# PROC091F_AOP_IO.net
KiCad netlist of a schematic drawn in Altium Designer
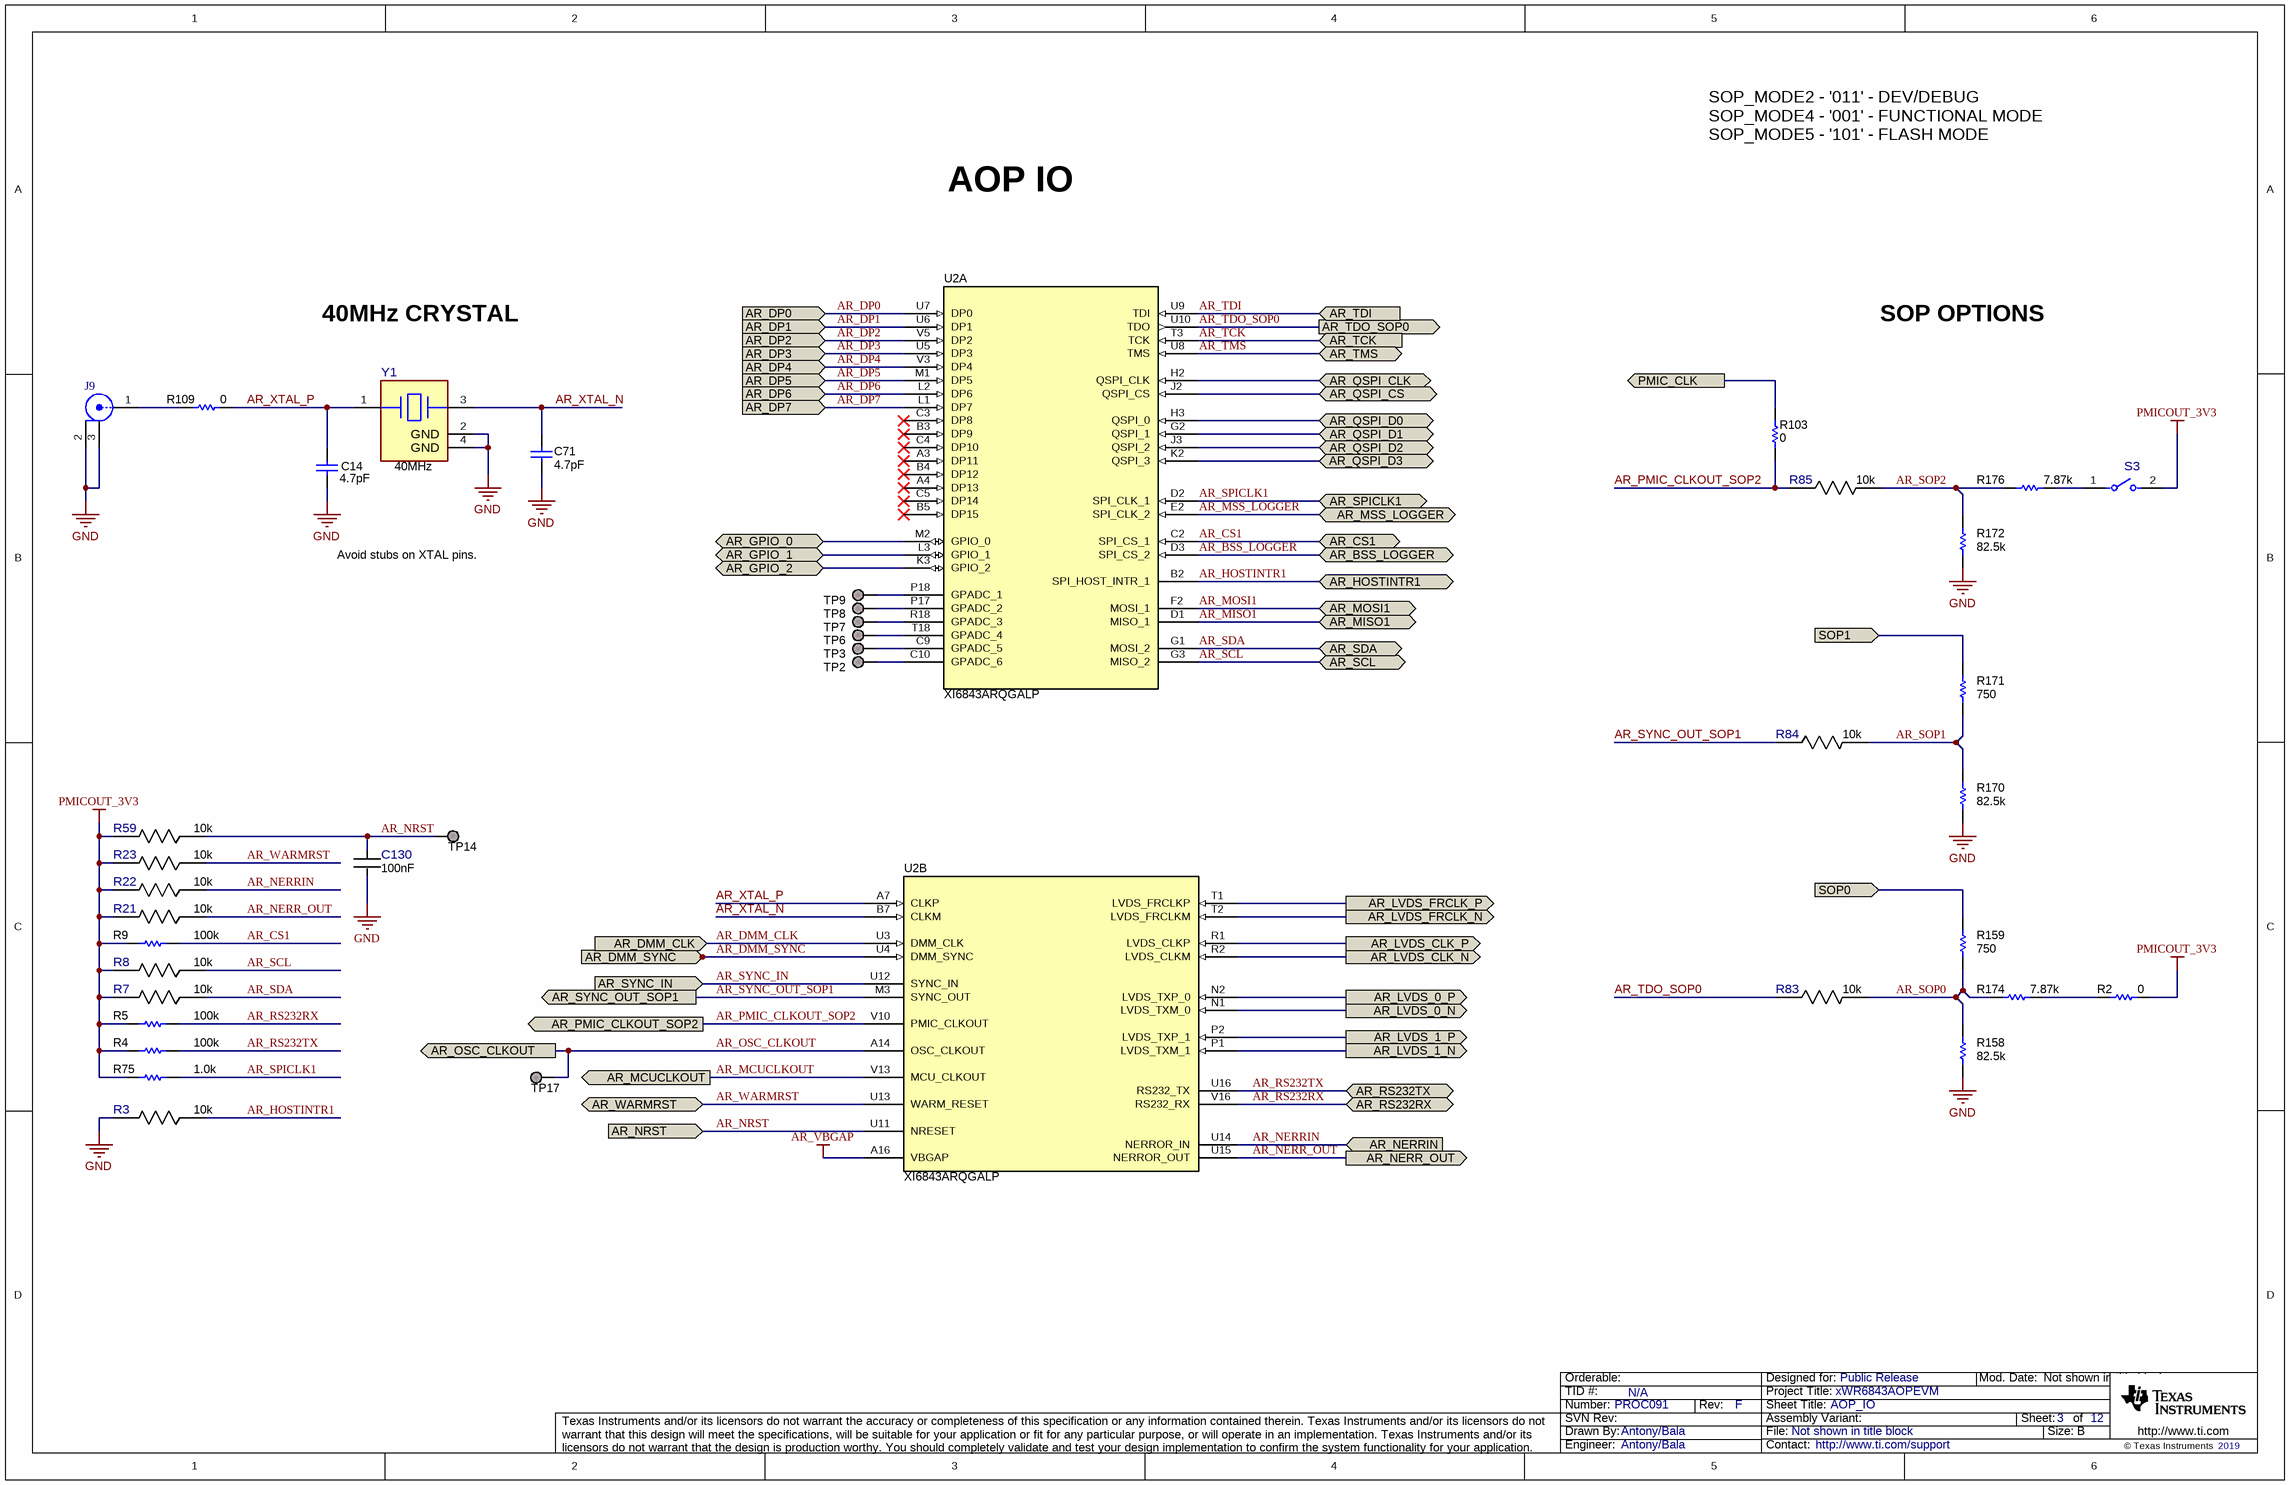
[diagram p0: PROC091F_AOP_IO.SchDoc]

(export (version "E")
  (design (tool "Eeschema 10.0.6"))
  (components
    (comp (ref "C14")
      (value "4.7pF")
      (footprint "0201_033L")
      (description "CAP, CERM, 4.7 pF, 50 V,+/- 3%, C0G/NP0, 0201")
      (fields (field (name "MANUFACTURER") "MuRata") (field (name "PARTNUMBER") "GRM0335C1H4R7BA01D"))
      (libsource (lib "Altium Vault - TI") (part "Capacitor"))
    )
    (comp (ref "C71")
      (value "4.7pF")
      (footprint "0201_033L")
      (description "CAP, CERM, 4.7 pF, 50 V,+/- 3%, C0G/NP0, 0201")
      (fields (field (name "MANUFACTURER") "MuRata") (field (name "PARTNUMBER") "GRM0335C1H4R7BA01D"))
      (libsource (lib "Altium Vault - TI") (part "Capacitor"))
    )
    (comp (ref "C130")
      (value "GRM033R6YA104KE14D")
      (footprint "FP-GRM033R6YA104KE14D_0201 (0603 Metric)-IPC_C")
      (description "Cap Ceramic 0.1uF 35V X5R 10% Pad SMD 0201 85C T/R")
      (fields (field (name "CAP_F") "100nF") (field (name "MANUFACTURER") "Murata Electronics North America"))
      (libsource (lib "Altium Vault - TI") (part "SYM-B32642B0223J"))
    )
    (comp (ref "J9")
      (value "U.FL-R-SMT-1(01)")
      (footprint "CONN_UFL-R-SMT-1")
      (description "Receptacle, Ultra Miniature Coaxial, Male Pin, 50 ohm, SMT")
      (fields
        (field (name "MANUFACTURER") "Hirose Electric Co. Ltd.")
        (field (name "PUBLISHER") "Texas Instruments")
      )
      (libsource (lib "Altium Vault - TI") (part "SMA_Contact1_GND23"))
    )
    (comp (ref "R2")
      (value "RC0201JR-070RL")
      (footprint "FP-RC0201JR-070RL_0201 (0603 Metric)-MFG")
      (description "RES SMD 0 OHM JUMPER 1/20W 0201")
      (fields (field (name "MANUFACTURER") "Yageo") (field (name "RES_OHM") "0"))
      (libsource (lib "Altium Vault - TI") (part "SYM-WSR3R1500F"))
    )
    (comp (ref "R3")
      (value "RR0306P-103-D")
      (footprint "FP-RR0306P-103-D_0201-IPC_C")
      (description "10 kOhms ±0.5% 0.05W, 1/20W Chip Resistor 0201 (0603 Metric)  Thin Film")
      (fields (field (name "MANUFACTURER") "Susumu") (field (name "RES_OHM") "10k"))
      (libsource (lib "Altium Vault - TI") (part "SYM-PMR18EZPJ000"))
    )
    (comp (ref "R4")
      (value "100k")
      (footprint "0201L")
      (description "RES, 100 k, 1%, 0.05 W, 0201")
      (fields (field (name "MANUFACTURER") "Vishay-Dale") (field (name "PARTNUMBER") "CRCW0201100KFKED"))
      (libsource (lib "Altium Vault - TI") (part "Resistor"))
    )
    (comp (ref "R5")
      (value "100k")
      (footprint "0201L")
      (description "RES, 100 k, 1%, 0.05 W, 0201")
      (fields (field (name "MANUFACTURER") "Vishay-Dale") (field (name "PARTNUMBER") "CRCW0201100KFKED"))
      (libsource (lib "Altium Vault - TI") (part "Resistor"))
    )
    (comp (ref "R7")
      (value "RR0306P-103-D")
      (footprint "FP-RR0306P-103-D_0201-IPC_C")
      (description "10 kOhms ±0.5% 0.05W, 1/20W Chip Resistor 0201 (0603 Metric)  Thin Film")
      (fields (field (name "MANUFACTURER") "Susumu") (field (name "RES_OHM") "10k"))
      (libsource (lib "Altium Vault - TI") (part "SYM-PMR18EZPJ000"))
    )
    (comp (ref "R8")
      (value "RR0306P-103-D")
      (footprint "FP-RR0306P-103-D_0201-IPC_C")
      (description "10 kOhms ±0.5% 0.05W, 1/20W Chip Resistor 0201 (0603 Metric)  Thin Film")
      (fields (field (name "MANUFACTURER") "Susumu") (field (name "RES_OHM") "10k"))
      (libsource (lib "Altium Vault - TI") (part "SYM-PMR18EZPJ000"))
    )
    (comp (ref "R9")
      (value "100k")
      (footprint "0201L")
      (description "RES, 100 k, 1%, 0.05 W, 0201")
      (fields (field (name "MANUFACTURER") "Vishay-Dale") (field (name "PARTNUMBER") "CRCW0201100KFKED"))
      (libsource (lib "Altium Vault - TI") (part "Resistor"))
    )
    (comp (ref "R21")
      (value "RR0306P-103-D")
      (footprint "FP-RR0306P-103-D_0201-IPC_C")
      (description "10 kOhms ±0.5% 0.05W, 1/20W Chip Resistor 0201 (0603 Metric)  Thin Film")
      (fields (field (name "MANUFACTURER") "Susumu") (field (name "RES_OHM") "10k"))
      (libsource (lib "Altium Vault - TI") (part "SYM-PMR18EZPJ000"))
    )
    (comp (ref "R22")
      (value "RR0306P-103-D")
      (footprint "FP-RR0306P-103-D_0201-IPC_C")
      (description "10 kOhms ±0.5% 0.05W, 1/20W Chip Resistor 0201 (0603 Metric)  Thin Film")
      (fields (field (name "MANUFACTURER") "Susumu") (field (name "RES_OHM") "10k"))
      (libsource (lib "Altium Vault - TI") (part "SYM-PMR18EZPJ000"))
    )
    (comp (ref "R23")
      (value "RR0306P-103-D")
      (footprint "FP-RR0306P-103-D_0201-IPC_C")
      (description "10 kOhms ±0.5% 0.05W, 1/20W Chip Resistor 0201 (0603 Metric)  Thin Film")
      (fields (field (name "MANUFACTURER") "Susumu") (field (name "RES_OHM") "10k"))
      (libsource (lib "Altium Vault - TI") (part "SYM-PMR18EZPJ000"))
    )
    (comp (ref "R59")
      (value "RR0306P-103-D")
      (footprint "FP-RR0306P-103-D_0201-IPC_C")
      (description "10 kOhms ±0.5% 0.05W, 1/20W Chip Resistor 0201 (0603 Metric)  Thin Film")
      (fields (field (name "MANUFACTURER") "Susumu") (field (name "RES_OHM") "10k"))
      (libsource (lib "Altium Vault - TI") (part "SYM-PMR18EZPJ000"))
    )
    (comp (ref "R75")
      (value "1.0k")
      (footprint "0201L")
      (description "RES, 1.0 k, 5%, 0.05 W, 0201")
      (fields
        (field (name "MANUFACTURER") "Yageo America")
        (field (name "PARTNUMBER") "RC0201JR-071KL")
        (field (name "PUBLISHER") "Texas Instruments")
      )
      (libsource (lib "Altium Vault - TI") (part "Resistor"))
    )
    (comp (ref "R83")
      (value "RR0306P-103-D")
      (footprint "FP-RR0306P-103-D_0201-IPC_C")
      (description "10 kOhms ±0.5% 0.05W, 1/20W Chip Resistor 0201 (0603 Metric)  Thin Film")
      (fields (field (name "MANUFACTURER") "Susumu") (field (name "RES_OHM") "10k"))
      (libsource (lib "Altium Vault - TI") (part "SYM-PMR18EZPJ000"))
    )
    (comp (ref "R84")
      (value "RR0306P-103-D")
      (footprint "FP-RR0306P-103-D_0201-IPC_C")
      (description "10 kOhms ±0.5% 0.05W, 1/20W Chip Resistor 0201 (0603 Metric)  Thin Film")
      (fields (field (name "MANUFACTURER") "Susumu") (field (name "RES_OHM") "10k"))
      (libsource (lib "Altium Vault - TI") (part "SYM-PMR18EZPJ000"))
    )
    (comp (ref "R85")
      (value "RR0306P-103-D")
      (footprint "FP-RR0306P-103-D_0201-IPC_C")
      (description "10 kOhms ±0.5% 0.05W, 1/20W Chip Resistor 0201 (0603 Metric)  Thin Film")
      (fields (field (name "MANUFACTURER") "Susumu") (field (name "RES_OHM") "10k"))
      (libsource (lib "Altium Vault - TI") (part "SYM-PMR18EZPJ000"))
    )
    (comp (ref "R103")
      (value "RC0201JR-070RL")
      (footprint "FP-RC0201JR-070RL_0201 (0603 Metric)-IPC_C")
      (description "RES SMD 0 OHM JUMPER 1/20W 0201")
      (fields (field (name "MANUFACTURER") "Yageo") (field (name "RES_OHM") "0"))
      (libsource (lib "Altium Vault - TI") (part "SYM-WSR3R1500F"))
    )
    (comp (ref "R109")
      (value "RC0201JR-070RL")
      (footprint "FP-RC0201JR-070RL_0201 (0603 Metric)-MFG")
      (description "RES SMD 0 OHM JUMPER 1/20W 0201")
      (fields (field (name "MANUFACTURER") "Yageo") (field (name "RES_OHM") "0"))
      (libsource (lib "Altium Vault - TI") (part "SYM-WSR3R1500F"))
    )
    (comp (ref "R158")
      (value "82.5k")
      (footprint "0201L")
      (description "RES, 82.5 k, 1%, 0.05 W, 0201")
      (fields
        (field (name "MANUFACTURER") "Yageo America")
        (field (name "PARTNUMBER") "RC0201FR-0782K5L")
        (field (name "PUBLISHER") "Texas Instruments")
      )
      (libsource (lib "Altium Vault - TI") (part "Resistor"))
    )
    (comp (ref "R159")
      (value "750")
      (footprint "0201L")
      (description "RES, 750, 5%, 0.05 W, 0201")
      (fields
        (field (name "MANUFACTURER") "Yageo America")
        (field (name "PARTNUMBER") "RC0201JR-07750RL")
        (field (name "PUBLISHER") "Texas Instruments")
      )
      (libsource (lib "Altium Vault - TI") (part "Resistor"))
    )
    (comp (ref "R170")
      (value "82.5k")
      (footprint "0201L")
      (description "RES, 82.5 k, 1%, 0.05 W, 0201")
      (fields
        (field (name "MANUFACTURER") "Yageo America")
        (field (name "PARTNUMBER") "RC0201FR-0782K5L")
        (field (name "PUBLISHER") "Texas Instruments")
      )
      (libsource (lib "Altium Vault - TI") (part "Resistor"))
    )
    (comp (ref "R171")
      (value "750")
      (footprint "0201L")
      (description "RES, 750, 5%, 0.05 W, 0201")
      (fields
        (field (name "MANUFACTURER") "Yageo America")
        (field (name "PARTNUMBER") "RC0201JR-07750RL")
        (field (name "PUBLISHER") "Texas Instruments")
      )
      (libsource (lib "Altium Vault - TI") (part "Resistor"))
    )
    (comp (ref "R172")
      (value "82.5k")
      (footprint "0201L")
      (description "RES, 82.5 k, 1%, 0.05 W, 0201")
      (fields
        (field (name "MANUFACTURER") "Yageo America")
        (field (name "PARTNUMBER") "RC0201FR-0782K5L")
        (field (name "PUBLISHER") "Texas Instruments")
      )
      (libsource (lib "Altium Vault - TI") (part "Resistor"))
    )
    (comp (ref "R174")
      (value "7.87k")
      (footprint "0201L")
      (description "RES, 7.87 k, 1%, 0.05 W, 0201")
      (fields
        (field (name "MANUFACTURER") "Yageo America")
        (field (name "PARTNUMBER") "RC0201FR-077K87L")
        (field (name "PUBLISHER") "Texas Instruments")
      )
      (libsource (lib "Altium Vault - TI") (part "Resistor"))
    )
    (comp (ref "R176")
      (value "7.87k")
      (footprint "0201L")
      (description "RES, 7.87 k, 1%, 0.05 W, 0201")
      (fields
        (field (name "MANUFACTURER") "Yageo America")
        (field (name "PARTNUMBER") "RC0201FR-077K87L")
        (field (name "PUBLISHER") "Texas Instruments")
      )
      (libsource (lib "Altium Vault - TI") (part "Resistor"))
    )
    (comp (ref "S3")
      (value "CHS-01TA")
      (footprint "FP-CHS-01TA_SMT_SW_5MM4_2MM5-MFG")
      (description "SWITCH SLIDE DIP SPST 100MA 6V")
      (fields (field (name "MANUFACTURER") "Nidec Copal Electronics"))
      (libsource (lib "Altium Vault - TI") (part "SYM-PTS635SK25SM"))
    )
    (comp (ref "TP2")
      (value "TESTPOINT")
      (footprint "TP_25MIL-SMT")
      (description "TEST POINT.  No entry in BOM.")
      (libsource (lib "Altium Vault - TI") (part "TESTPOINT"))
    )
    (comp (ref "TP3")
      (value "TESTPOINT")
      (footprint "TP_25MIL-SMT")
      (description "TEST POINT.  No entry in BOM.")
      (libsource (lib "Altium Vault - TI") (part "TESTPOINT"))
    )
    (comp (ref "TP6")
      (value "TESTPOINT")
      (footprint "TP_25MIL-SMT")
      (description "TEST POINT.  No entry in BOM.")
      (libsource (lib "Altium Vault - TI") (part "TESTPOINT"))
    )
    (comp (ref "TP7")
      (value "TESTPOINT")
      (footprint "TP_25MIL-SMT")
      (description "TEST POINT.  No entry in BOM.")
      (libsource (lib "Altium Vault - TI") (part "TESTPOINT"))
    )
    (comp (ref "TP8")
      (value "TESTPOINT")
      (footprint "TP_25MIL-SMT")
      (description "TEST POINT.  No entry in BOM.")
      (libsource (lib "Altium Vault - TI") (part "TESTPOINT"))
    )
    (comp (ref "TP9")
      (value "TESTPOINT")
      (footprint "TP_25MIL-SMT")
      (description "TEST POINT.  No entry in BOM.")
      (libsource (lib "Altium Vault - TI") (part "TESTPOINT"))
    )
    (comp (ref "TP14")
      (value "TESTPOINT")
      (footprint "TP_25MIL-SMT")
      (description "TEST POINT.  No entry in BOM.")
      (libsource (lib "Altium Vault - TI") (part "TESTPOINT"))
    )
    (comp (ref "TP17")
      (value "TESTPOINT")
      (footprint "TP_25MIL-SMT")
      (description "TEST POINT.  No entry in BOM.")
      (libsource (lib "Altium Vault - TI") (part "TESTPOINT"))
    )
    (comp (ref "U2")
      (value "XI6843ARQGALP")
      (footprint "ALP0180A")
      (description "XI6843ARQGALP, ALP0180A (BGA-180)")
      (fields (field (name "MANUFACTURER") "Texas Instruments") (field (name "PARTNUMBER") "XI6843ARQGALP"))
      (libsource (lib "Altium Vault - TI") (part "XI6843ARQGALP"))
    )
    (comp (ref "Y1")
      (value "CX2016DB40000D0FLJCC")
      (footprint "FP-CX2016DB40000D0FLJCC_SMT_2MM0_1MM6-MFG")
      (description "CRYSTAL 40.0000MHZ 8PF SMD")
      (fields
        (field (name "FREQUENCY_FIXED") "40MHz")
        (field (name "MANUFACTURER") "Kyocera International Inc. Electronic Components")
      )
      (libsource (lib "Altium Vault - TI") (part "SYM-CX2016DB40000D0FLJCC"))
    )
  )
  (nets
    (net (code "1") (name "/AR_BSS_LOGGER") (class "Default")
      (node (ref "U2") (pin "D3") (pinfunction "SPI_CS_2_D3") (pintype "input"))
    )
    (net (code "2") (name "/AR_CS1") (class "Default")
      (node (ref "R9") (pin "2") (pinfunction "2_2") (pintype "passive"))
      (node (ref "U2") (pin "C2") (pinfunction "SPI_CS_1_C2") (pintype "input"))
    )
    (net (code "3") (name "/AR_DMM_CLK") (class "Default")
      (node (ref "U2") (pin "U3") (pinfunction "DMM_CLK_U3") (pintype "input"))
    )
    (net (code "4") (name "/AR_DMM_SYNC") (class "Default")
      (node (ref "U2") (pin "U4") (pinfunction "DMM_SYNC_U4") (pintype "input"))
    )
    (net (code "5") (name "/AR_DP0") (class "Default")
      (node (ref "U2") (pin "U7") (pinfunction "DP0_U7") (pintype "input"))
    )
    (net (code "6") (name "/AR_DP1") (class "Default")
      (node (ref "U2") (pin "U6") (pinfunction "DP1_U6") (pintype "input"))
    )
    (net (code "7") (name "/AR_DP2") (class "Default")
      (node (ref "U2") (pin "V5") (pinfunction "DP2_V5") (pintype "input"))
    )
    (net (code "8") (name "/AR_DP3") (class "Default")
      (node (ref "U2") (pin "U5") (pinfunction "DP3_U5") (pintype "input"))
    )
    (net (code "9") (name "/AR_DP4") (class "Default")
      (node (ref "U2") (pin "V3") (pinfunction "DP4_V3") (pintype "input"))
    )
    (net (code "10") (name "/AR_DP5") (class "Default")
      (node (ref "U2") (pin "M1") (pinfunction "DP5_M1") (pintype "input"))
    )
    (net (code "11") (name "/AR_DP6") (class "Default")
      (node (ref "U2") (pin "L2") (pinfunction "DP6_L2") (pintype "input"))
    )
    (net (code "12") (name "/AR_DP7") (class "Default")
      (node (ref "U2") (pin "L1") (pinfunction "DP7_L1") (pintype "input"))
    )
    (net (code "13") (name "/AR_GPIO_0") (class "Default")
      (node (ref "U2") (pin "M2") (pinfunction "GPIO_0_M2") (pintype "bidirectional"))
    )
    (net (code "14") (name "/AR_GPIO_1") (class "Default")
      (node (ref "U2") (pin "L3") (pinfunction "GPIO_1_L3") (pintype "bidirectional"))
    )
    (net (code "15") (name "/AR_GPIO_2") (class "Default")
      (node (ref "U2") (pin "K3") (pinfunction "GPIO_2_K3") (pintype "bidirectional"))
    )
    (net (code "16") (name "/AR_HOSTINTR1") (class "Default")
      (node (ref "R3") (pin "1") (pinfunction "1_1") (pintype "passive"))
      (node (ref "U2") (pin "B2") (pinfunction "SPI_HOST_INTR_1_B2") (pintype "passive"))
    )
    (net (code "17") (name "/AR_LVDS_0_N") (class "Default")
      (node (ref "U2") (pin "N1") (pinfunction "LVDS_TXM_0_N1") (pintype "input"))
    )
    (net (code "18") (name "/AR_LVDS_0_P") (class "Default")
      (node (ref "U2") (pin "N2") (pinfunction "LVDS_TXP_0_N2") (pintype "input"))
    )
    (net (code "19") (name "/AR_LVDS_1_N") (class "Default")
      (node (ref "U2") (pin "P1") (pinfunction "LVDS_TXM_1_P1") (pintype "input"))
    )
    (net (code "20") (name "/AR_LVDS_1_P") (class "Default")
      (node (ref "U2") (pin "P2") (pinfunction "LVDS_TXP_1_P2") (pintype "input"))
    )
    (net (code "21") (name "/AR_LVDS_CLK_N") (class "Default")
      (node (ref "U2") (pin "R2") (pinfunction "LVDS_CLKM_R2") (pintype "input"))
    )
    (net (code "22") (name "/AR_LVDS_CLK_P") (class "Default")
      (node (ref "U2") (pin "R1") (pinfunction "LVDS_CLKP_R1") (pintype "input"))
    )
    (net (code "23") (name "/AR_LVDS_FRCLK_N") (class "Default")
      (node (ref "U2") (pin "T2") (pinfunction "LVDS_FRCLKM_T2") (pintype "input"))
    )
    (net (code "24") (name "/AR_LVDS_FRCLK_P") (class "Default")
      (node (ref "U2") (pin "T1") (pinfunction "LVDS_FRCLKP_T1") (pintype "input"))
    )
    (net (code "25") (name "/AR_MCUCLKOUT") (class "Default")
      (node (ref "U2") (pin "V13") (pinfunction "MCU_CLKOUT_V13") (pintype "passive"))
    )
    (net (code "26") (name "/AR_MISO1") (class "Default")
      (node (ref "U2") (pin "D1") (pinfunction "MISO_1_D1") (pintype "passive"))
    )
    (net (code "27") (name "/AR_MOSI1") (class "Default")
      (node (ref "U2") (pin "F2") (pinfunction "MOSI_1_F2") (pintype "passive"))
    )
    (net (code "28") (name "/AR_MSS_LOGGER") (class "Default")
      (node (ref "U2") (pin "E2") (pinfunction "SPI_CLK_2_E2") (pintype "input"))
    )
    (net (code "29") (name "/AR_NERRIN") (class "Default")
      (node (ref "R22") (pin "1") (pinfunction "1_1") (pintype "passive"))
      (node (ref "U2") (pin "U14") (pinfunction "NERROR_IN_U14") (pintype "passive"))
    )
    (net (code "30") (name "/AR_NERR_OUT") (class "Default")
      (node (ref "R21") (pin "1") (pinfunction "1_1") (pintype "passive"))
      (node (ref "U2") (pin "U15") (pinfunction "NERROR_OUT_U15") (pintype "passive"))
    )
    (net (code "31") (name "/AR_NRST") (class "Default")
      (node (ref "C130") (pin "1") (pinfunction "1_1") (pintype "passive"))
      (node (ref "R59") (pin "1") (pinfunction "1_1") (pintype "passive"))
      (node (ref "TP14") (pin "1") (pintype "passive"))
      (node (ref "U2") (pin "U11") (pinfunction "NRESET_U11") (pintype "passive"))
    )
    (net (code "32") (name "/AR_OSC_CLKOUT") (class "Default")
      (node (ref "TP17") (pin "1") (pintype "passive"))
      (node (ref "U2") (pin "A14") (pinfunction "OSC_CLKOUT_A14") (pintype "passive"))
    )
    (net (code "33") (name "/AR_PMIC_CLKOUT_SOP2") (class "Default")
      (node (ref "R103") (pin "1") (pinfunction "1_1") (pintype "passive"))
      (node (ref "R85") (pin "1") (pinfunction "1_1") (pintype "passive"))
      (node (ref "U2") (pin "V10") (pinfunction "PMIC_CLKOUT_V10") (pintype "passive"))
    )
    (net (code "34") (name "/AR_QSPI_CLK") (class "Default")
      (node (ref "U2") (pin "H2") (pinfunction "QSPI_CLK_H2") (pintype "input"))
    )
    (net (code "35") (name "/AR_QSPI_CS") (class "Default")
      (node (ref "U2") (pin "J2") (pinfunction "QSPI_CS_J2") (pintype "input"))
    )
    (net (code "36") (name "/AR_QSPI_D0") (class "Default")
      (node (ref "U2") (pin "H3") (pinfunction "QSPI_0_H3") (pintype "input"))
    )
    (net (code "37") (name "/AR_QSPI_D1") (class "Default")
      (node (ref "U2") (pin "G2") (pinfunction "QSPI_1_G2") (pintype "input"))
    )
    (net (code "38") (name "/AR_QSPI_D2") (class "Default")
      (node (ref "U2") (pin "J3") (pinfunction "QSPI_2_J3") (pintype "input"))
    )
    (net (code "39") (name "/AR_QSPI_D3") (class "Default")
      (node (ref "U2") (pin "K2") (pinfunction "QSPI_3_K2") (pintype "input"))
    )
    (net (code "40") (name "/AR_RS232RX") (class "Default")
      (node (ref "R5") (pin "2") (pinfunction "2_2") (pintype "passive"))
      (node (ref "U2") (pin "V16") (pinfunction "RS232_RX_V16") (pintype "passive"))
    )
    (net (code "41") (name "/AR_RS232TX") (class "Default")
      (node (ref "R4") (pin "2") (pinfunction "2_2") (pintype "passive"))
      (node (ref "U2") (pin "U16") (pinfunction "RS232_TX_U16") (pintype "passive"))
    )
    (net (code "42") (name "/AR_SCL") (class "Default")
      (node (ref "R8") (pin "1") (pinfunction "1_1") (pintype "passive"))
      (node (ref "U2") (pin "G3") (pinfunction "MISO_2_G3") (pintype "passive"))
    )
    (net (code "43") (name "/AR_SDA") (class "Default")
      (node (ref "R7") (pin "1") (pinfunction "1_1") (pintype "passive"))
      (node (ref "U2") (pin "G1") (pinfunction "MOSI_2_G1") (pintype "passive"))
    )
    (net (code "44") (name "/AR_SOP0") (class "Default")
      (node (ref "R158") (pin "2") (pinfunction "2_2") (pintype "passive"))
      (node (ref "R159") (pin "1") (pinfunction "1_1") (pintype "passive"))
      (node (ref "R174") (pin "2") (pinfunction "2_2") (pintype "passive"))
      (node (ref "R83") (pin "2") (pinfunction "2_2") (pintype "passive"))
    )
    (net (code "45") (name "/AR_SOP1") (class "Default")
      (node (ref "R170") (pin "2") (pinfunction "2_2") (pintype "passive"))
      (node (ref "R171") (pin "1") (pinfunction "1_1") (pintype "passive"))
      (node (ref "R84") (pin "2") (pinfunction "2_2") (pintype "passive"))
    )
    (net (code "46") (name "/AR_SOP2") (class "Default")
      (node (ref "R172") (pin "2") (pinfunction "2_2") (pintype "passive"))
      (node (ref "R176") (pin "2") (pinfunction "2_2") (pintype "passive"))
      (node (ref "R85") (pin "2") (pinfunction "2_2") (pintype "passive"))
    )
    (net (code "47") (name "/AR_SPICLK1") (class "Default")
      (node (ref "R75") (pin "2") (pinfunction "2_2") (pintype "passive"))
      (node (ref "U2") (pin "D2") (pinfunction "SPI_CLK_1_D2") (pintype "input"))
    )
    (net (code "48") (name "/AR_SYNC_IN") (class "Default")
      (node (ref "U2") (pin "U12") (pinfunction "SYNC_IN_U12") (pintype "passive"))
    )
    (net (code "49") (name "/AR_SYNC_OUT_SOP1") (class "Default")
      (node (ref "R84") (pin "1") (pinfunction "1_1") (pintype "passive"))
      (node (ref "U2") (pin "M3") (pinfunction "SYNC_OUT_M3") (pintype "passive"))
    )
    (net (code "50") (name "/AR_TCK") (class "Default")
      (node (ref "U2") (pin "T3") (pinfunction "TCK_T3") (pintype "input"))
    )
    (net (code "51") (name "/AR_TDI") (class "Default")
      (node (ref "U2") (pin "U9") (pinfunction "TDI_U9") (pintype "input"))
    )
    (net (code "52") (name "/AR_TDO_SOP0") (class "Default")
      (node (ref "R83") (pin "1") (pinfunction "1_1") (pintype "passive"))
      (node (ref "U2") (pin "U10") (pinfunction "TDO_U10") (pintype "output"))
    )
    (net (code "53") (name "/AR_TMS") (class "Default")
      (node (ref "U2") (pin "U8") (pinfunction "TMS_U8") (pintype "input"))
    )
    (net (code "54") (name "/AR_WARMRST") (class "Default")
      (node (ref "R23") (pin "1") (pinfunction "1_1") (pintype "passive"))
      (node (ref "U2") (pin "U13") (pinfunction "WARM_RESET_U13") (pintype "passive"))
    )
    (net (code "55") (name "/AR_XTAL_N") (class "Default")
      (node (ref "C71") (pin "2") (pinfunction "2_2") (pintype "passive"))
      (node (ref "U2") (pin "B7") (pinfunction "CLKM_B7") (pintype "input"))
      (node (ref "Y1") (pin "3") (pinfunction "3_3") (pintype "passive"))
    )
    (net (code "56") (name "/AR_XTAL_P") (class "Default")
      (node (ref "C14") (pin "2") (pinfunction "2_2") (pintype "passive"))
      (node (ref "R109") (pin "1") (pinfunction "1_1") (pintype "passive"))
      (node (ref "U2") (pin "A7") (pinfunction "CLKP_A7") (pintype "input"))
      (node (ref "Y1") (pin "1") (pinfunction "1_1") (pintype "passive"))
    )
    (net (code "57") (name "/PMIC_CLK") (class "Default")
      (node (ref "R103") (pin "2") (pinfunction "2_2") (pintype "passive"))
    )
    (net (code "58") (name "/SOP0") (class "Default")
      (node (ref "R159") (pin "2") (pinfunction "2_2") (pintype "passive"))
    )
    (net (code "59") (name "/SOP1") (class "Default")
      (node (ref "R171") (pin "2") (pinfunction "2_2") (pintype "passive"))
    )
    (net (code "60") (name "AR_VBGAP") (class "Default")
      (node (ref "U2") (pin "A16") (pinfunction "VBGAP_A16") (pintype "passive"))
    )
    (net (code "61") (name "GND") (class "Default")
      (node (ref "C130") (pin "2") (pinfunction "2_2") (pintype "passive"))
      (node (ref "C14") (pin "1") (pinfunction "1_1") (pintype "passive"))
      (node (ref "C71") (pin "1") (pinfunction "1_1") (pintype "passive"))
      (node (ref "J9") (pin "2") (pinfunction "2_2") (pintype "passive"))
      (node (ref "J9") (pin "3") (pinfunction "3_3") (pintype "passive"))
      (node (ref "R158") (pin "1") (pinfunction "1_1") (pintype "passive"))
      (node (ref "R170") (pin "1") (pinfunction "1_1") (pintype "passive"))
      (node (ref "R172") (pin "1") (pinfunction "1_1") (pintype "passive"))
      (node (ref "R3") (pin "2") (pinfunction "2_2") (pintype "passive"))
      (node (ref "Y1") (pin "2") (pinfunction "GND_2") (pintype "power_in"))
      (node (ref "Y1") (pin "4") (pinfunction "GND_4") (pintype "power_in"))
    )
    (net (code "62") (name "Net-(J9-Pad1)") (class "Default")
      (node (ref "J9") (pin "1") (pinfunction "1_1") (pintype "passive"))
      (node (ref "R109") (pin "2") (pinfunction "2_2") (pintype "passive"))
    )
    (net (code "63") (name "Net-(R174-Pad1)") (class "Default")
      (node (ref "R174") (pin "1") (pinfunction "1_1") (pintype "passive"))
      (node (ref "R2") (pin "2") (pinfunction "2_2") (pintype "passive"))
    )
    (net (code "64") (name "Net-(R176-Pad1)") (class "Default")
      (node (ref "R176") (pin "1") (pinfunction "1_1") (pintype "passive"))
      (node (ref "S3") (pin "1") (pinfunction "1_1") (pintype "passive"))
    )
    (net (code "65") (name "Net-(U2A-GPADC_1)") (class "Default")
      (node (ref "TP9") (pin "1") (pintype "passive"))
      (node (ref "U2") (pin "P18") (pinfunction "GPADC_1_P18") (pintype "passive"))
    )
    (net (code "66") (name "Net-(U2A-GPADC_2)") (class "Default")
      (node (ref "TP8") (pin "1") (pintype "passive"))
      (node (ref "U2") (pin "P17") (pinfunction "GPADC_2_P17") (pintype "passive"))
    )
    (net (code "67") (name "Net-(U2A-GPADC_3)") (class "Default")
      (node (ref "TP7") (pin "1") (pintype "passive"))
      (node (ref "U2") (pin "R18") (pinfunction "GPADC_3_R18") (pintype "passive"))
    )
    (net (code "68") (name "Net-(U2A-GPADC_4)") (class "Default")
      (node (ref "TP6") (pin "1") (pintype "passive"))
      (node (ref "U2") (pin "T18") (pinfunction "GPADC_4_T18") (pintype "passive"))
    )
    (net (code "69") (name "Net-(U2A-GPADC_5)") (class "Default")
      (node (ref "TP3") (pin "1") (pintype "passive"))
      (node (ref "U2") (pin "C9") (pinfunction "GPADC_5_C9") (pintype "passive"))
    )
    (net (code "70") (name "Net-(U2A-GPADC_6)") (class "Default")
      (node (ref "TP2") (pin "1") (pintype "passive"))
      (node (ref "U2") (pin "C10") (pinfunction "GPADC_6_C10") (pintype "passive"))
    )
    (net (code "71") (name "PMICOUT_3V3") (class "Default")
      (node (ref "R2") (pin "1") (pinfunction "1_1") (pintype "passive"))
      (node (ref "R21") (pin "2") (pinfunction "2_2") (pintype "passive"))
      (node (ref "R22") (pin "2") (pinfunction "2_2") (pintype "passive"))
      (node (ref "R23") (pin "2") (pinfunction "2_2") (pintype "passive"))
      (node (ref "R4") (pin "1") (pinfunction "1_1") (pintype "passive"))
      (node (ref "R5") (pin "1") (pinfunction "1_1") (pintype "passive"))
      (node (ref "R59") (pin "2") (pinfunction "2_2") (pintype "passive"))
      (node (ref "R7") (pin "2") (pinfunction "2_2") (pintype "passive"))
      (node (ref "R75") (pin "1") (pinfunction "1_1") (pintype "passive"))
      (node (ref "R8") (pin "2") (pinfunction "2_2") (pintype "passive"))
      (node (ref "R9") (pin "1") (pinfunction "1_1") (pintype "passive"))
      (node (ref "S3") (pin "2") (pinfunction "2_2") (pintype "passive"))
    )
    (net (code "72") (name "unconnected-(U2A-DP8-PadC3)") (class "Default")
      (node (ref "U2") (pin "C3") (pinfunction "DP8_C3") (pintype "input+no_connect"))
    )
    (net (code "73") (name "unconnected-(U2A-DP9-PadB3)") (class "Default")
      (node (ref "U2") (pin "B3") (pinfunction "DP9_B3") (pintype "input+no_connect"))
    )
    (net (code "74") (name "unconnected-(U2A-DP10-PadC4)") (class "Default")
      (node (ref "U2") (pin "C4") (pinfunction "DP10_C4") (pintype "input+no_connect"))
    )
    (net (code "75") (name "unconnected-(U2A-DP11-PadA3)") (class "Default")
      (node (ref "U2") (pin "A3") (pinfunction "DP11_A3") (pintype "input+no_connect"))
    )
    (net (code "76") (name "unconnected-(U2A-DP12-PadB4)") (class "Default")
      (node (ref "U2") (pin "B4") (pinfunction "DP12_B4") (pintype "input+no_connect"))
    )
    (net (code "77") (name "unconnected-(U2A-DP13-PadA4)") (class "Default")
      (node (ref "U2") (pin "A4") (pinfunction "DP13_A4") (pintype "input+no_connect"))
    )
    (net (code "78") (name "unconnected-(U2A-DP14-PadC5)") (class "Default")
      (node (ref "U2") (pin "C5") (pinfunction "DP14_C5") (pintype "input+no_connect"))
    )
    (net (code "79") (name "unconnected-(U2A-DP15-PadB5)") (class "Default")
      (node (ref "U2") (pin "B5") (pinfunction "DP15_B5") (pintype "input+no_connect"))
    )
  )
)
